# Nextion_bridge.net
KiCad netlist of a schematic drawn in Altium Designer
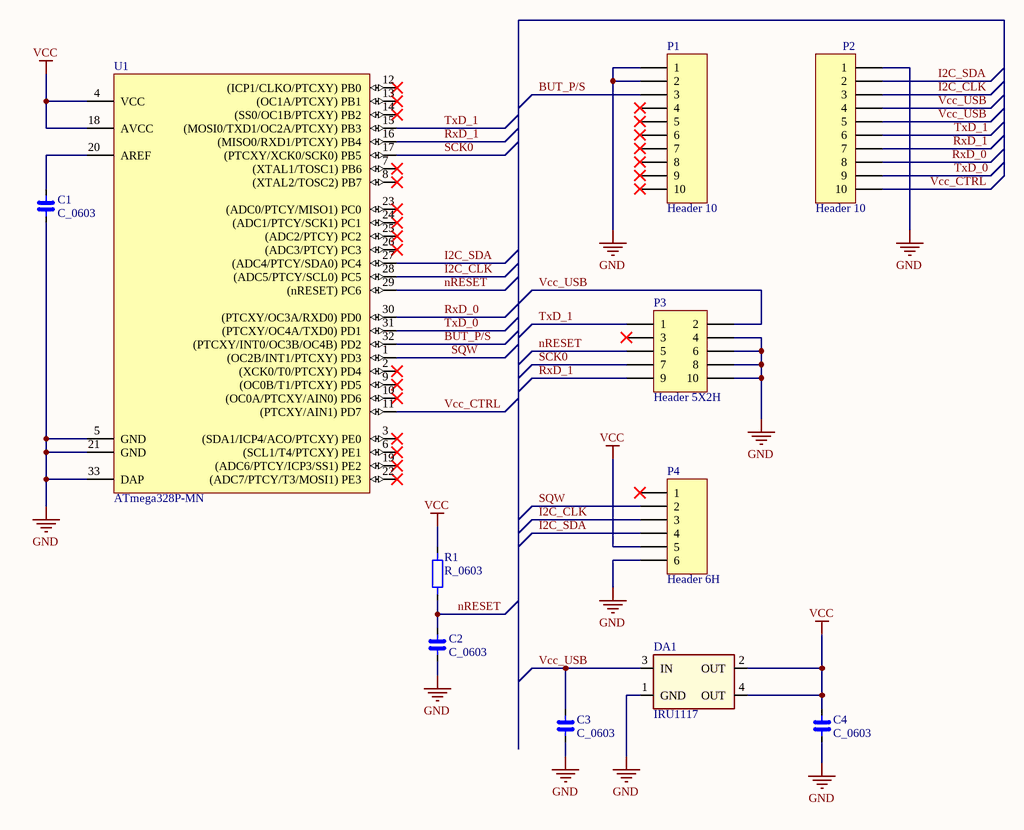
[diagram p0: Nextion bridge.SchDoc]

(export (version "E")
  (design (tool "Eeschema 10.0.6"))
  (components
    (comp (ref "C1")
      (value "C_0603")
      (footprint "SM/C_0603")
      (fields
        (field (name "VOLTAGE") "50V")
        (field (name "MANUFACTURER") "AVX")
        (field (name "TOLERANCE") "±20%")
      )
      (libsource (lib "MyLib") (part "C_0603"))
    )
    (comp (ref "C2")
      (value "C_0603")
      (footprint "SM/C_0603")
      (fields
        (field (name "VOLTAGE") "50V")
        (field (name "MANUFACTURER") "AVX")
        (field (name "TOLERANCE") "±20%")
      )
      (libsource (lib "MyLib") (part "C_0603"))
    )
    (comp (ref "C3")
      (value "C_0603")
      (footprint "SM/C_0603")
      (fields
        (field (name "VOLTAGE") "50V")
        (field (name "MANUFACTURER") "AVX")
        (field (name "TOLERANCE") "±20%")
      )
      (libsource (lib "MyLib") (part "C_0603"))
    )
    (comp (ref "C4")
      (value "C_0603")
      (footprint "SM/C_0603")
      (fields
        (field (name "VOLTAGE") "50V")
        (field (name "MANUFACTURER") "AVX")
        (field (name "TOLERANCE") "±20%")
      )
      (libsource (lib "MyLib") (part "C_0603"))
    )
    (comp (ref "DA1") (value "IRU1117") (footprint "SOT223") (libsource (lib "MyLib") (part "IRU1117")))
    (comp (ref "P1")
      (value "Header 10")
      (footprint "HDR1X10")
      (description "Header, 10-Pin")
      (fields (field (name "PUBLISHER") "Altium Limited"))
      (libsource (lib "") (part "Header 10_1"))
    )
    (comp (ref "P2")
      (value "Header 10")
      (footprint "HDR1X10")
      (description "Header, 10-Pin")
      (fields (field (name "PUBLISHER") "Altium Limited"))
      (libsource (lib "Miscellaneous Connectors") (part "Header 10"))
    )
    (comp (ref "P3")
      (value "Header 5X2H")
      (footprint "HDR2X5H")
      (description "Header, 5-Pin, Dual row, Right Angle")
      (fields (field (name "PUBLISHER") "Altium Limited"))
      (libsource (lib "Miscellaneous Connectors") (part "Header 5X2H"))
    )
    (comp (ref "P4")
      (value "Header 6H")
      (footprint "HDR1X6H")
      (description "Header, 6-Pin, Right Angle")
      (fields (field (name "PUBLISHER") "Altium Limited"))
      (libsource (lib "Miscellaneous Connectors") (part "Header 6H"))
    )
    (comp (ref "R1")
      (value "R_0603")
      (footprint "SM/R_0603")
      (fields
        (field (name "TOLERANCE") "±5%")
        (field (name "MANUFACTURER") "YAGEO")
        (field (name "POWER") "1/10W")
      )
      (libsource (lib "MyLib") (part "R_0603"))
    )
    (comp (ref "U1")
      (value "ATmega328P-MN")
      (footprint "32M1-A_N")
      (libsource (lib "Nextion bridge") (part "ATmega328P-MN"))
    )
  )
  (nets
    (net (code "1") (name "/BUT_P{slash}S") (class "Default")
      (node (ref "P1") (pin "3") (pinfunction "3_3") (pintype "passive"))
      (node (ref "U1") (pin "32") (pinfunction "(PTCXY/INT0/OC3B/OC4B)_PD2_32") (pintype "bidirectional"))
    )
    (net (code "2") (name "/I2C_CLK") (class "Default")
      (node (ref "P2") (pin "3") (pinfunction "3_3") (pintype "passive"))
      (node (ref "P4") (pin "3") (pinfunction "3_3") (pintype "passive"))
      (node (ref "U1") (pin "28") (pinfunction "(ADC5/PTCY/SCL0)_PC5_28") (pintype "bidirectional"))
    )
    (net (code "3") (name "/I2C_SDA") (class "Default")
      (node (ref "P2") (pin "2") (pinfunction "2_2") (pintype "passive"))
      (node (ref "P4") (pin "4") (pinfunction "4_4") (pintype "passive"))
      (node (ref "U1") (pin "27") (pinfunction "(ADC4/PTCY/SDA0)_PC4_27") (pintype "bidirectional"))
    )
    (net (code "4") (name "/RxD_0") (class "Default")
      (node (ref "P2") (pin "8") (pinfunction "8_8") (pintype "passive"))
      (node (ref "U1") (pin "30") (pinfunction "(PTCXY/OC3A/RXD0)_PD0_30") (pintype "bidirectional"))
    )
    (net (code "5") (name "/RxD_1") (class "Default")
      (node (ref "P2") (pin "7") (pinfunction "7_7") (pintype "passive"))
      (node (ref "P3") (pin "9") (pinfunction "9_9") (pintype "passive"))
      (node (ref "U1") (pin "16") (pinfunction "(MISO0/RXD1/PTCXY)_PB4_16") (pintype "bidirectional"))
    )
    (net (code "6") (name "/SCK0") (class "Default")
      (node (ref "P3") (pin "7") (pinfunction "7_7") (pintype "passive"))
      (node (ref "U1") (pin "17") (pinfunction "(PTCXY/XCK0/SCK0)_PB5_17") (pintype "bidirectional"))
    )
    (net (code "7") (name "/SQW") (class "Default")
      (node (ref "P4") (pin "2") (pinfunction "2_2") (pintype "passive"))
      (node (ref "U1") (pin "1") (pinfunction "(OC2B/INT1/PTCXY)_PD3_1") (pintype "bidirectional"))
    )
    (net (code "8") (name "/TxD_0") (class "Default")
      (node (ref "P2") (pin "9") (pinfunction "9_9") (pintype "passive"))
      (node (ref "U1") (pin "31") (pinfunction "(PTCXY/OC4A/TXD0)_PD1_31") (pintype "bidirectional"))
    )
    (net (code "9") (name "/TxD_1") (class "Default")
      (node (ref "P2") (pin "6") (pinfunction "6_6") (pintype "passive"))
      (node (ref "P3") (pin "1") (pinfunction "1_1") (pintype "passive"))
      (node (ref "U1") (pin "15") (pinfunction "(MOSI0/TXD1/OC2A/PTCXY)_PB3_15") (pintype "bidirectional"))
    )
    (net (code "10") (name "/Vcc_CTRL") (class "Default")
      (node (ref "P2") (pin "10") (pinfunction "10_10") (pintype "passive"))
      (node (ref "U1") (pin "11") (pinfunction "(PTCXY/AIN1)_PD7_11") (pintype "bidirectional"))
    )
    (net (code "11") (name "/Vcc_USB") (class "Default")
      (node (ref "C3") (pin "1") (pinfunction "1_1") (pintype "passive"))
      (node (ref "DA1") (pin "3") (pinfunction "IN_3") (pintype "passive"))
      (node (ref "P2") (pin "4") (pinfunction "4_4") (pintype "passive"))
      (node (ref "P2") (pin "5") (pinfunction "5_5") (pintype "passive"))
      (node (ref "P3") (pin "2") (pinfunction "2_2") (pintype "passive"))
    )
    (net (code "12") (name "/nRESET") (class "Default")
      (node (ref "C2") (pin "1") (pinfunction "1_1") (pintype "passive"))
      (node (ref "P3") (pin "5") (pinfunction "5_5") (pintype "passive"))
      (node (ref "R1") (pin "1") (pinfunction "1_1") (pintype "passive"))
      (node (ref "U1") (pin "29") (pinfunction "(nRESET)_PC6_29") (pintype "bidirectional"))
    )
    (net (code "13") (name "GND") (class "Default")
      (node (ref "C1") (pin "2") (pinfunction "2_2") (pintype "passive"))
      (node (ref "C2") (pin "2") (pinfunction "2_2") (pintype "passive"))
      (node (ref "C3") (pin "2") (pinfunction "2_2") (pintype "passive"))
      (node (ref "C4") (pin "2") (pinfunction "2_2") (pintype "passive"))
      (node (ref "DA1") (pin "1") (pinfunction "GND_1") (pintype "passive"))
      (node (ref "P1") (pin "1") (pinfunction "1_1") (pintype "passive"))
      (node (ref "P1") (pin "2") (pinfunction "2_2") (pintype "passive"))
      (node (ref "P2") (pin "1") (pinfunction "1_1") (pintype "passive"))
      (node (ref "P3") (pin "10") (pinfunction "10_10") (pintype "passive"))
      (node (ref "P3") (pin "4") (pinfunction "4_4") (pintype "passive"))
      (node (ref "P3") (pin "6") (pinfunction "6_6") (pintype "passive"))
      (node (ref "P3") (pin "8") (pinfunction "8_8") (pintype "passive"))
      (node (ref "P4") (pin "6") (pinfunction "6_6") (pintype "passive"))
      (node (ref "U1") (pin "21") (pinfunction "GND_21") (pintype "power_in"))
      (node (ref "U1") (pin "33") (pinfunction "DAP_33") (pintype "power_in"))
      (node (ref "U1") (pin "5") (pinfunction "GND_5") (pintype "power_in"))
    )
    (net (code "14") (name "Net-(U1-AREF)") (class "Default")
      (node (ref "C1") (pin "1") (pinfunction "1_1") (pintype "passive"))
      (node (ref "U1") (pin "20") (pinfunction "AREF_20") (pintype "passive"))
    )
    (net (code "15") (name "VCC") (class "Default")
      (node (ref "C4") (pin "1") (pinfunction "1_1") (pintype "passive"))
      (node (ref "DA1") (pin "2") (pinfunction "OUT_2") (pintype "passive"))
      (node (ref "DA1") (pin "4") (pinfunction "OUT_4") (pintype "passive"))
      (node (ref "P4") (pin "5") (pinfunction "5_5") (pintype "passive"))
      (node (ref "R1") (pin "2") (pinfunction "2_2") (pintype "passive"))
      (node (ref "U1") (pin "18") (pinfunction "AVCC_18") (pintype "power_in"))
      (node (ref "U1") (pin "4") (pinfunction "VCC_4") (pintype "power_in"))
    )
    (net (code "16") (name "unconnected-(P1-Pad4)") (class "Default")
      (node (ref "P1") (pin "4") (pinfunction "4_4") (pintype "passive+no_connect"))
    )
    (net (code "17") (name "unconnected-(P1-Pad5)") (class "Default")
      (node (ref "P1") (pin "5") (pinfunction "5_5") (pintype "passive+no_connect"))
    )
    (net (code "18") (name "unconnected-(P1-Pad6)") (class "Default")
      (node (ref "P1") (pin "6") (pinfunction "6_6") (pintype "passive+no_connect"))
    )
    (net (code "19") (name "unconnected-(P1-Pad7)") (class "Default")
      (node (ref "P1") (pin "7") (pinfunction "7_7") (pintype "passive+no_connect"))
    )
    (net (code "20") (name "unconnected-(P1-Pad8)") (class "Default")
      (node (ref "P1") (pin "8") (pinfunction "8_8") (pintype "passive+no_connect"))
    )
    (net (code "21") (name "unconnected-(P1-Pad9)") (class "Default")
      (node (ref "P1") (pin "9") (pinfunction "9_9") (pintype "passive+no_connect"))
    )
    (net (code "22") (name "unconnected-(P1-Pad10)") (class "Default")
      (node (ref "P1") (pin "10") (pinfunction "10_10") (pintype "passive+no_connect"))
    )
    (net (code "23") (name "unconnected-(P3-Pad3)") (class "Default")
      (node (ref "P3") (pin "3") (pinfunction "3_3") (pintype "passive+no_connect"))
    )
    (net (code "24") (name "unconnected-(P4-Pad1)") (class "Default")
      (node (ref "P4") (pin "1") (pinfunction "1_1") (pintype "passive+no_connect"))
    )
    (net (code "25") (name "unconnected-(U1-(ADC0{slash}PTCY{slash}MISO1)_PC0-Pad23)") (class "Default")
      (node (ref "U1") (pin "23") (pinfunction "(ADC0/PTCY/MISO1)_PC0_23") (pintype "bidirectional+no_connect"))
    )
    (net (code "26") (name "unconnected-(U1-(ADC1{slash}PTCY{slash}SCK1)_PC1-Pad24)") (class "Default")
      (node (ref "U1") (pin "24") (pinfunction "(ADC1/PTCY/SCK1)_PC1_24") (pintype "bidirectional+no_connect"))
    )
    (net (code "27") (name "unconnected-(U1-(ADC2{slash}PTCY)_PC2-Pad25)") (class "Default")
      (node (ref "U1") (pin "25") (pinfunction "(ADC2/PTCY)_PC2_25") (pintype "bidirectional+no_connect"))
    )
    (net (code "28") (name "unconnected-(U1-(ADC3{slash}PTCY)_PC3-Pad26)") (class "Default")
      (node (ref "U1") (pin "26") (pinfunction "(ADC3/PTCY)_PC3_26") (pintype "bidirectional+no_connect"))
    )
    (net (code "29") (name "unconnected-(U1-(ADC6{slash}PTCY{slash}ICP3{slash}SS1)_PE2-Pad19)") (class "Default")
      (node (ref "U1") (pin "19") (pinfunction "(ADC6/PTCY/ICP3/SS1)_PE2_19") (pintype "bidirectional+no_connect"))
    )
    (net (code "30") (name "unconnected-(U1-(ADC7{slash}PTCY{slash}T3{slash}MOSI1)_PE3-Pad22)") (class "Default")
      (node (ref "U1") (pin "22") (pinfunction "(ADC7/PTCY/T3/MOSI1)_PE3_22") (pintype "bidirectional+no_connect"))
    )
    (net (code "31") (name "unconnected-(U1-(ICP1{slash}CLKO{slash}PTCXY)_PB0-Pad12)") (class "Default")
      (node (ref "U1") (pin "12") (pinfunction "(ICP1/CLKO/PTCXY)_PB0_12") (pintype "bidirectional+no_connect"))
    )
    (net (code "32") (name "unconnected-(U1-(OC0A{slash}PTCXY{slash}AIN0)_PD6-Pad10)") (class "Default")
      (node (ref "U1") (pin "10") (pinfunction "(OC0A/PTCXY/AIN0)_PD6_10") (pintype "bidirectional+no_connect"))
    )
    (net (code "33") (name "unconnected-(U1-(OC0B{slash}T1{slash}PTCXY)_PD5-Pad9)") (class "Default")
      (node (ref "U1") (pin "9") (pinfunction "(OC0B/T1/PTCXY)_PD5_9") (pintype "bidirectional+no_connect"))
    )
    (net (code "34") (name "unconnected-(U1-(OC1A{slash}PTCXY)_PB1-Pad13)") (class "Default")
      (node (ref "U1") (pin "13") (pinfunction "(OC1A/PTCXY)_PB1_13") (pintype "bidirectional+no_connect"))
    )
    (net (code "35") (name "unconnected-(U1-(SCL1{slash}T4{slash}PTCXY)_PE1-Pad6)") (class "Default")
      (node (ref "U1") (pin "6") (pinfunction "(SCL1/T4/PTCXY)_PE1_6") (pintype "bidirectional+no_connect"))
    )
    (net (code "36") (name "unconnected-(U1-(SDA1{slash}ICP4{slash}ACO{slash}PTCXY)_PE0-Pad3)") (class "Default")
      (node (ref "U1") (pin "3") (pinfunction "(SDA1/ICP4/ACO/PTCXY)_PE0_3") (pintype "bidirectional+no_connect"))
    )
    (net (code "37") (name "unconnected-(U1-(SS0{slash}OC1B{slash}PTCXY)_PB2-Pad14)") (class "Default")
      (node (ref "U1") (pin "14") (pinfunction "(SS0/OC1B/PTCXY)_PB2_14") (pintype "bidirectional+no_connect"))
    )
    (net (code "38") (name "unconnected-(U1-(XCK0{slash}T0{slash}PTCXY)_PD4-Pad2)") (class "Default")
      (node (ref "U1") (pin "2") (pinfunction "(XCK0/T0/PTCXY)_PD4_2") (pintype "bidirectional+no_connect"))
    )
    (net (code "39") (name "unconnected-(U1-(XTAL1{slash}TOSC1)_PB6-Pad7)") (class "Default")
      (node (ref "U1") (pin "7") (pinfunction "(XTAL1/TOSC1)_PB6_7") (pintype "bidirectional+no_connect"))
    )
    (net (code "40") (name "unconnected-(U1-(XTAL2{slash}TOSC2)_PB7-Pad8)") (class "Default")
      (node (ref "U1") (pin "8") (pinfunction "(XTAL2/TOSC2)_PB7_8") (pintype "bidirectional+no_connect"))
    )
  )
)
